# SchematZasilanie.net
KiCad netlist of a schematic drawn in EAGLE
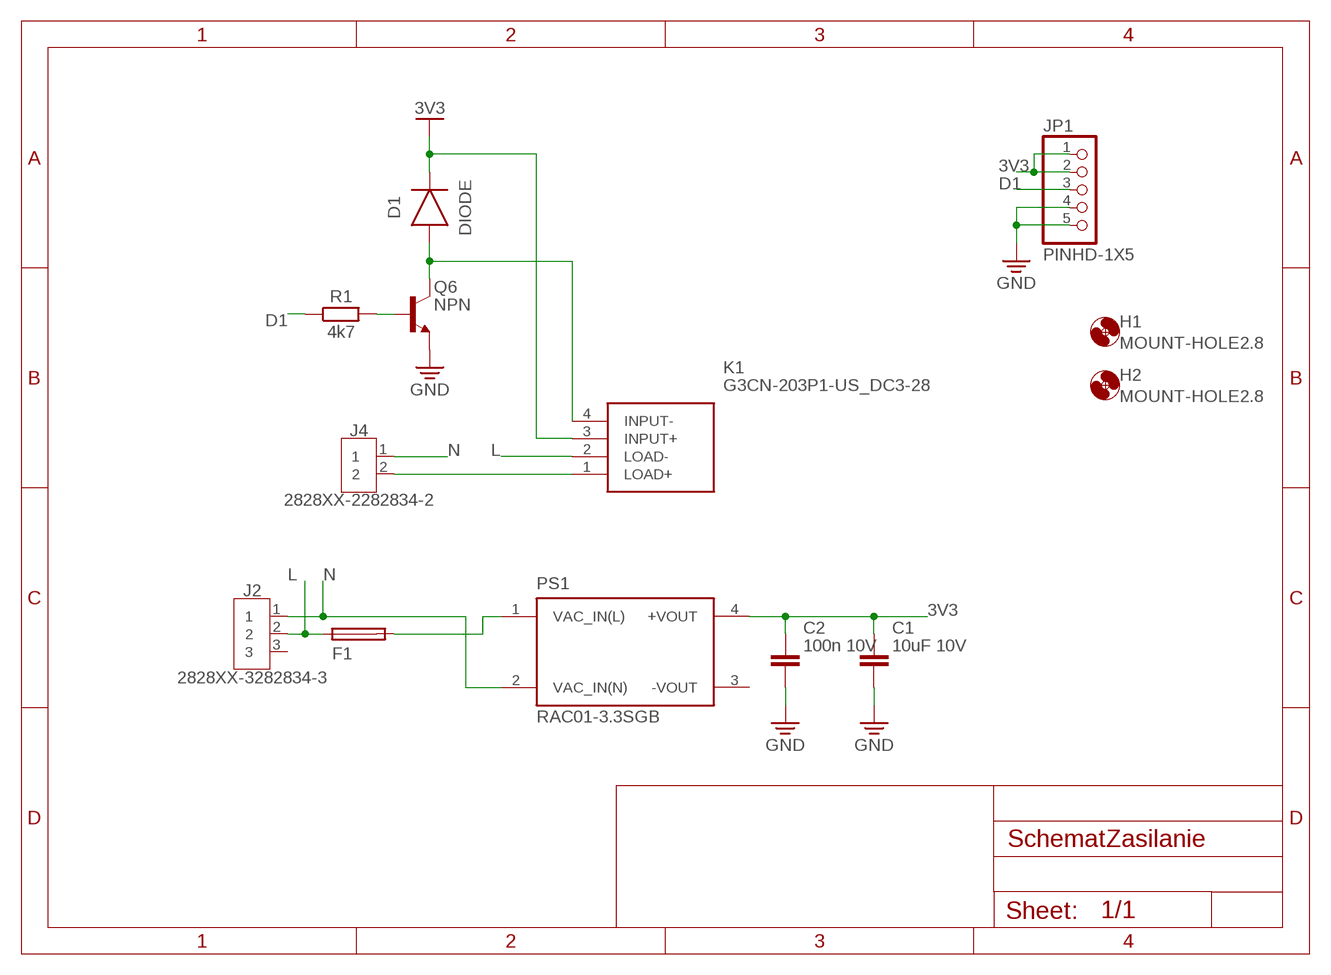
[diagram p0: schematic, sheet 1]

(export (version "E")
  (design (tool "Eeschema 10.0.6"))
  (components
    (comp (ref "C1")
      (value "10uF 10V")
      (footprint "eagle-import:CAPC3216X135")
      (libsource (lib "eagle-import") (part "CCHIP-1206(3216-METRIC)_"))
    )
    (comp (ref "C2")
      (value "100n 10V")
      (footprint "eagle-import:CAPC3216X135")
      (libsource (lib "eagle-import") (part "CCHIP-1206(3216-METRIC)_"))
    )
    (comp (ref "D1")
      (value "DIODE")
      (footprint "eagle-import:DIOMELF3516")
      (libsource (lib "eagle-import") (part "DIODEDO-213AA(SOD-80)_"))
    )
    (comp (ref "F1")
      (value "FUSE_CHIP-1206(3216-METRIC)")
      (footprint "eagle-import:FUSC3215X82N")
      (libsource (lib "eagle-import") (part "FUSECHIP-1206(3216-METRIC)_"))
    )
    (comp (ref "H1")
      (value "MOUNT-HOLE2.8")
      (footprint "eagle-import:2,8")
      (libsource (lib "eagle-import") (part "MOUNT-HOLE2.8"))
    )
    (comp (ref "H2")
      (value "MOUNT-HOLE2.8")
      (footprint "eagle-import:2,8")
      (libsource (lib "eagle-import") (part "MOUNT-HOLE2.8"))
    )
    (comp (ref "J2")
      (value "2828XX-3282834-3")
      (footprint "eagle-import:TERMBLK_254-3N")
      (fields (field (name "MANUFACTURER") "TE Connectivity AMP Connectors") (field (name "MPN") "282834-3"))
      (libsource (lib "eagle-import") (part "2828XX-3282834-3"))
    )
    (comp (ref "J4")
      (value "2828XX-2282834-2")
      (footprint "eagle-import:TERMBLK_254-2N")
      (fields (field (name "MANUFACTURER") "TE Connectivity AMP Connectors") (field (name "MPN") "282834-2 "))
      (libsource (lib "eagle-import") (part "2828XX-2282834-2"))
    )
    (comp (ref "JP1")
      (value "PINHD-1X5")
      (footprint "eagle-import:1X05")
      (fields (field (name "MANUFACTURER") "Generic"))
      (libsource (lib "eagle-import") (part "PINHD-1X5"))
    )
    (comp (ref "K1")
      (value "G3CN-203P1-US_DC3-28")
      (footprint "eagle-import:G3CN203P1USDC328")
      (fields
        (field (name "MANUFACTURER_PART_NUMBER") "G3CN-203P1-US DC3-28")
        (field (name "MOUSER_PART_NUMBER") "653-G3CN203P1USDC328")
      )
      (libsource (lib "eagle-import") (part "G3CN-203P1-US_DC3-28"))
    )
    (comp (ref "PS1")
      (value "RAC01-3.3SGB")
      (footprint "eagle-import:CONV_RAC01-3.3SGB")
      (fields (field (name "MF") "Recom Power") (field (name "MP") "RAC01-05SGB"))
      (libsource (lib "eagle-import") (part "RAC01-3.3SGB"))
    )
    (comp (ref "Q6")
      (value "NPN")
      (footprint "eagle-import:TO18")
      (libsource (lib "eagle-import") (part "NPNTO18-EBC_"))
    )
    (comp (ref "R1")
      (value "4k7")
      (footprint "eagle-import:RESC1608X60")
      (libsource (lib "eagle-import") (part "RCHIP-0603(1608-METRIC)_"))
    )
  )
  (nets
    (net (code "1") (name "/D1") (class "Default")
      (node (ref "JP1") (pin "3") (pinfunction "3_3") (pintype "passive"))
      (node (ref "R1") (pin "1") (pinfunction "1_1") (pintype "passive"))
    )
    (net (code "2") (name "/L") (class "Default")
      (node (ref "F1") (pin "1") (pinfunction "1_1") (pintype "passive"))
      (node (ref "J2") (pin "2") (pinfunction "2_2") (pintype "bidirectional"))
      (node (ref "K1") (pin "2") (pinfunction "LOAD-_2") (pintype "bidirectional"))
    )
    (net (code "3") (name "/N") (class "Default")
      (node (ref "J2") (pin "1") (pinfunction "1_1") (pintype "bidirectional"))
      (node (ref "J4") (pin "1") (pinfunction "1_1") (pintype "bidirectional"))
      (node (ref "PS1") (pin "2") (pinfunction "VAC_IN(N)_2") (pintype "input"))
    )
    (net (code "4") (name "3V3") (class "Default")
      (node (ref "C1") (pin "1") (pinfunction "1_1") (pintype "passive"))
      (node (ref "C2") (pin "1") (pinfunction "1_1") (pintype "passive"))
      (node (ref "D1") (pin "1") (pinfunction "C_1") (pintype "passive"))
      (node (ref "JP1") (pin "1") (pinfunction "1_1") (pintype "passive"))
      (node (ref "JP1") (pin "2") (pinfunction "2_2") (pintype "passive"))
      (node (ref "K1") (pin "3") (pinfunction "INPUT+_3") (pintype "bidirectional"))
      (node (ref "PS1") (pin "4") (pinfunction "+VOUT_4") (pintype "output"))
    )
    (net (code "5") (name "GND") (class "Default")
      (node (ref "C1") (pin "2") (pinfunction "2_2") (pintype "passive"))
      (node (ref "C2") (pin "2") (pinfunction "2_2") (pintype "passive"))
      (node (ref "JP1") (pin "4") (pinfunction "4_4") (pintype "passive"))
      (node (ref "JP1") (pin "5") (pinfunction "5_5") (pintype "passive"))
      (node (ref "Q6") (pin "1") (pinfunction "E_1") (pintype "passive"))
    )
    (net (code "6") (name "Net-(D1-A)") (class "Default")
      (node (ref "D1") (pin "2") (pinfunction "A_2") (pintype "passive"))
      (node (ref "K1") (pin "4") (pinfunction "INPUT-_4") (pintype "bidirectional"))
      (node (ref "Q6") (pin "3") (pinfunction "C_3") (pintype "passive"))
    )
    (net (code "7") (name "Net-(K1-LOAD+)") (class "Default")
      (node (ref "J4") (pin "2") (pinfunction "2_2") (pintype "bidirectional"))
      (node (ref "K1") (pin "1") (pinfunction "LOAD+_1") (pintype "bidirectional"))
    )
    (net (code "8") (name "Net-(PS1-VAC_IN(L))") (class "Default")
      (node (ref "F1") (pin "2") (pinfunction "2_2") (pintype "passive"))
      (node (ref "PS1") (pin "1") (pinfunction "VAC_IN(L)_1") (pintype "input"))
    )
    (net (code "9") (name "Net-(Q6-B)") (class "Default")
      (node (ref "Q6") (pin "2") (pinfunction "B_2") (pintype "passive"))
      (node (ref "R1") (pin "2") (pinfunction "2_2") (pintype "passive"))
    )
    (net (code "10") (name "unconnected-(J2-Pad3)") (class "Default")
      (node (ref "J2") (pin "3") (pinfunction "3_3") (pintype "bidirectional"))
    )
    (net (code "11") (name "unconnected-(PS1--VOUT-Pad3)") (class "Default")
      (node (ref "PS1") (pin "3") (pinfunction "-VOUT_3") (pintype "output"))
    )
  )
)
